# S3.net
KiCad netlist of a schematic drawn in EasyEDA Pro
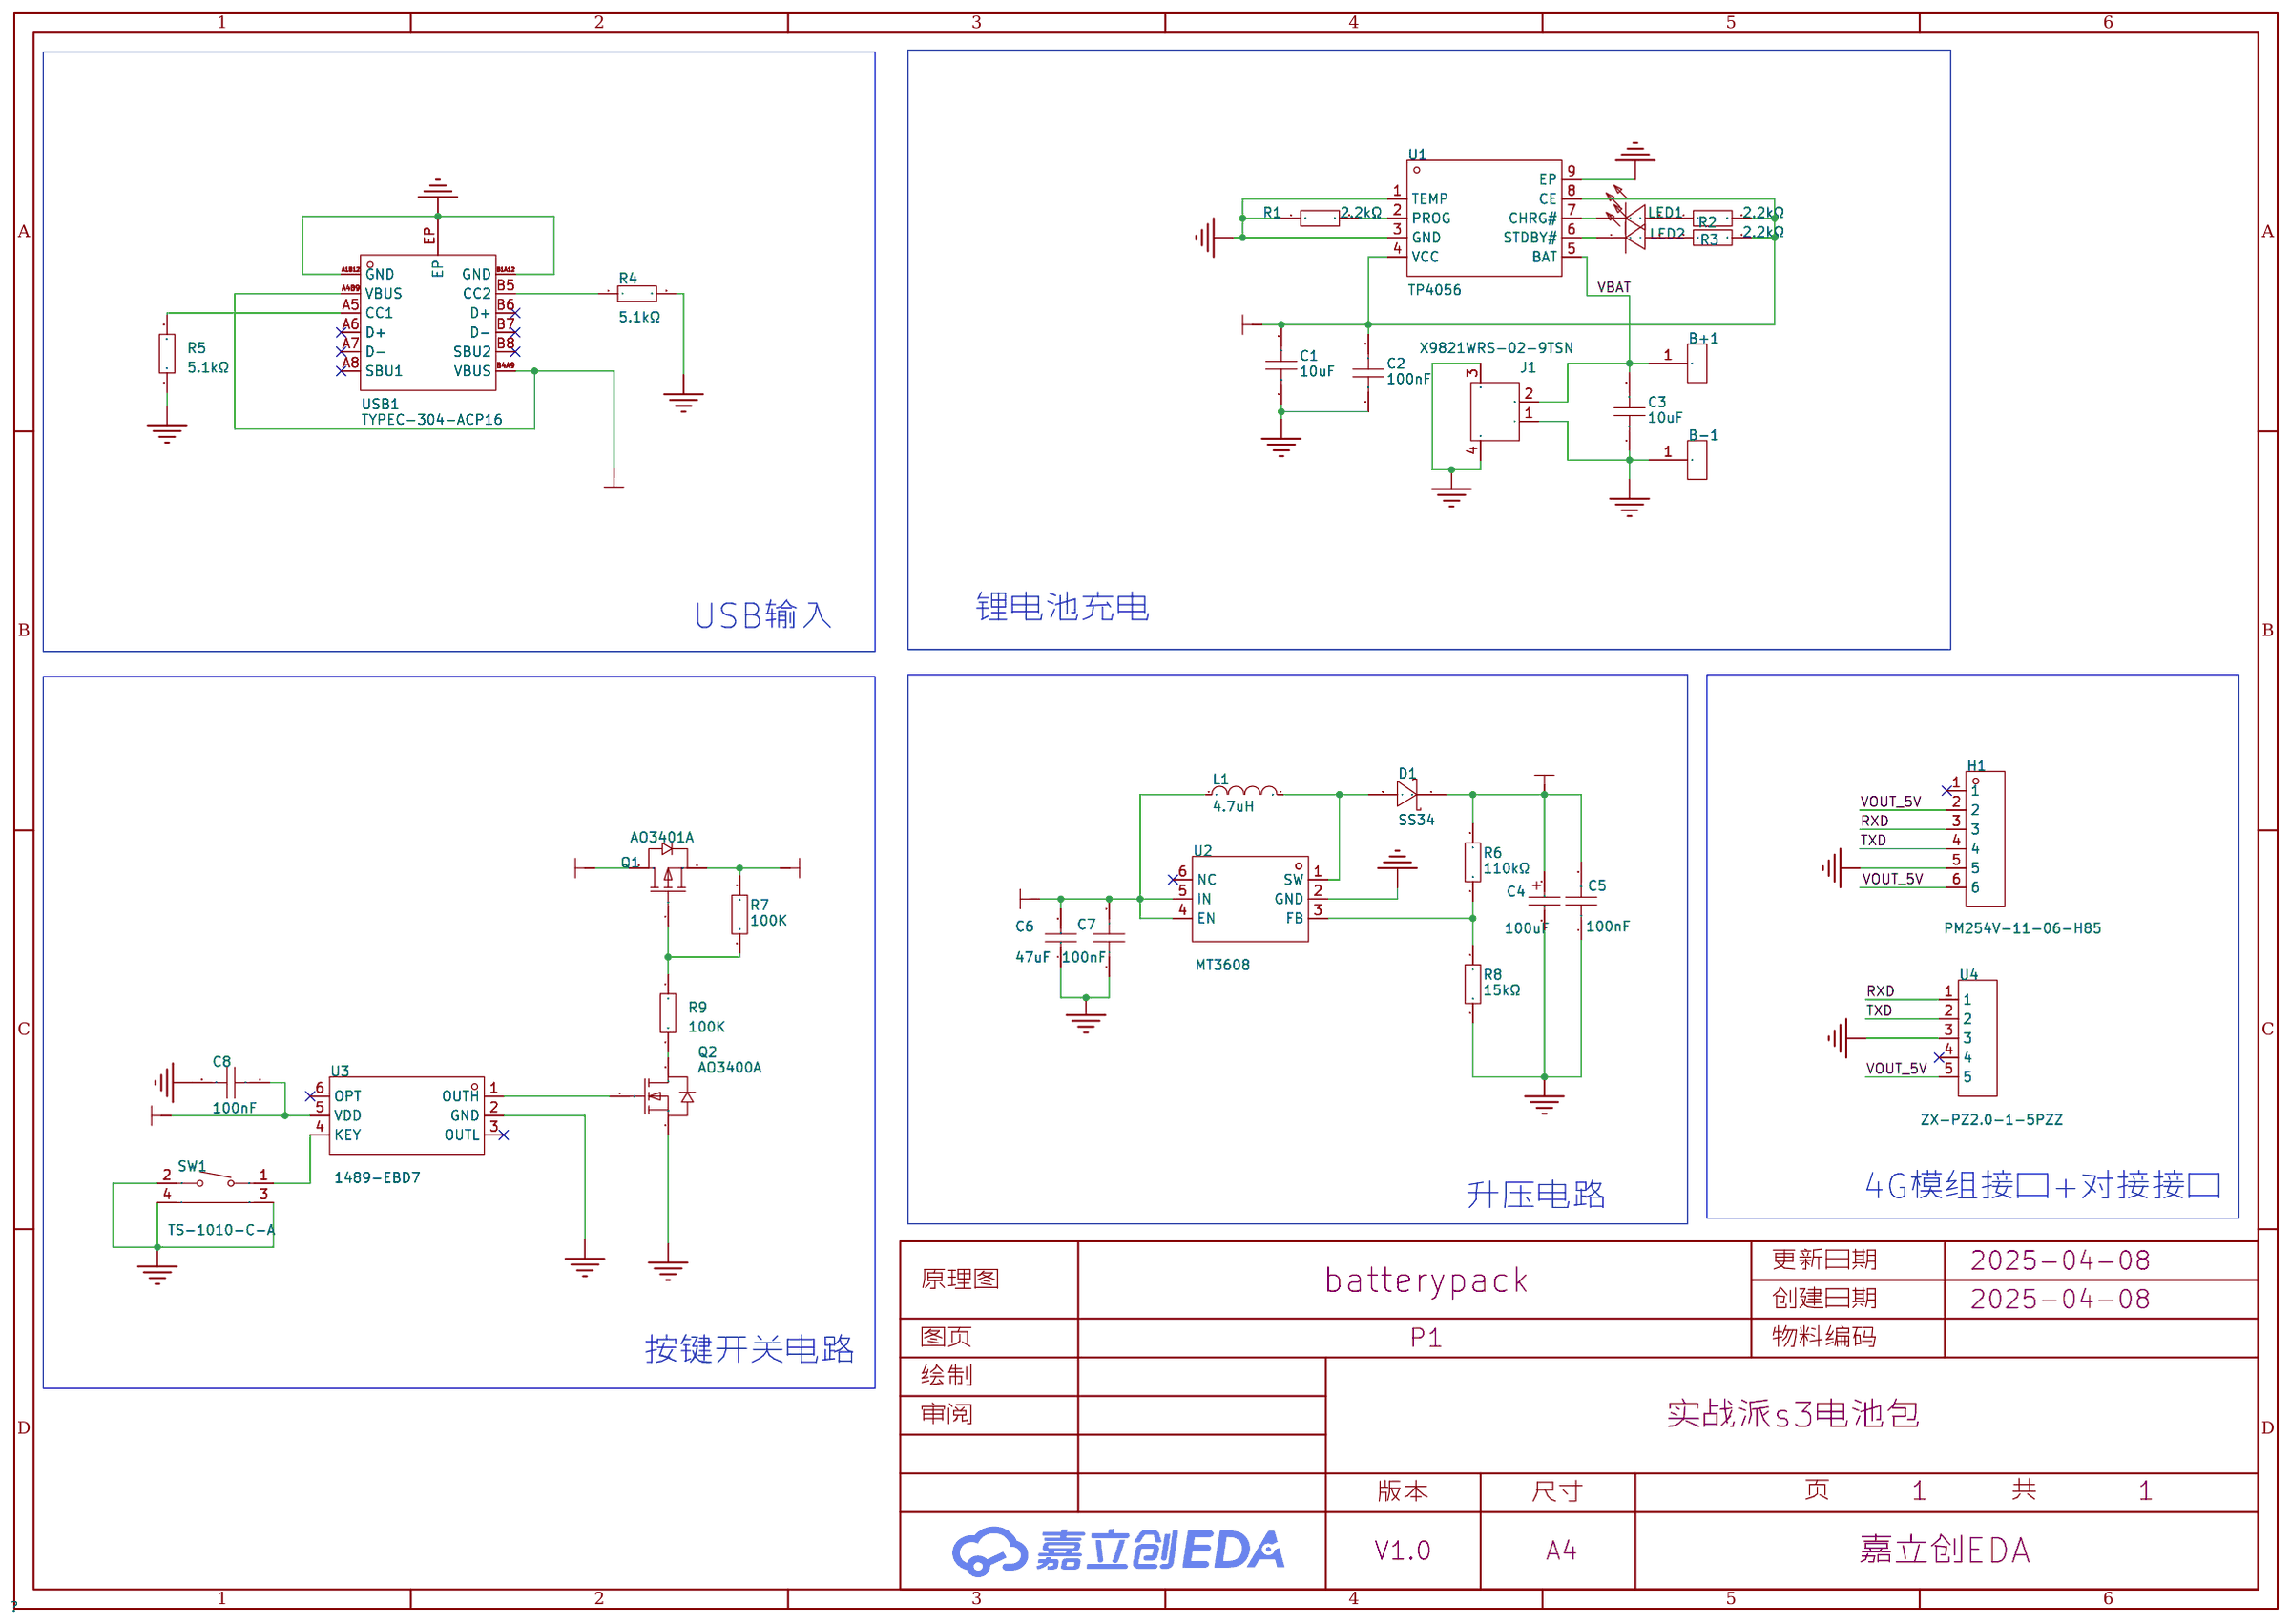
[diagram p0: schematic sheet]

(export (version "E")
  (design (tool "Eeschema 10.0.6"))
  (components
    (comp (ref "B+1")
      (value "~")
      (footprint "easyedapro:test_point")
      (libsource (lib "easyedapro") (part "test_point"))
    )
    (comp (ref "B-1")
      (value "~")
      (footprint "easyedapro:test_point")
      (libsource (lib "easyedapro") (part "test_point"))
    )
    (comp (ref "C1")
      (value "10uF")
      (fields
        (field (name "Manufacturer Part") "CL10A106KP8NNNC")
        (field (name "Manufacturer") "SAMSUNG(三星)")
      )
      (libsource (lib "easyedapro") (part "CL21A106KAYNNNE"))
    )
    (comp (ref "C2")
      (value "100nF")
      (footprint "easyedapro:C0402")
      (description "容值:100nF;精度:±10%;额定电压:50V;材质(温度系数):X7R;")
      (fields
        (field (name "Manufacturer Part") "CL05B104KB54PNC")
        (field (name "Manufacturer") "SAMSUNG(三星)")
      )
      (libsource (lib "easyedapro") (part "CL05B104KB54PNC"))
    )
    (comp (ref "C3")
      (value "10uF")
      (fields
        (field (name "Manufacturer Part") "CL10A106KP8NNNC")
        (field (name "Manufacturer") "SAMSUNG(三星)")
      )
      (libsource (lib "easyedapro") (part "CL21A106KAYNNNE"))
    )
    (comp (ref "C4")
      (value "100uF")
      (footprint "easyedapro:CASE-B_3528")
      (description "容值:100uF;精度:±10%;额定电压:6.3V;等效串联电阻:1.7Ω@100kHz;")
      (fields (field (name "Manufacturer Part") "TAJB107K006RNJ") (field (name "Manufacturer") "Kyocera AVX"))
      (libsource (lib "easyedapro") (part "TAJB107K006RNJ"))
    )
    (comp (ref "C5")
      (value "100nF")
      (fields
        (field (name "Manufacturer Part") "CL05B104KB54PNC")
        (field (name "Manufacturer") "SAMSUNG(三星)")
      )
      (libsource (lib "easyedapro") (part "CGA0603X7R104K500JT"))
    )
    (comp (ref "C6")
      (value "47uF")
      (footprint "easyedapro:C0805")
      (description "容值:47uF;精度:±20%;额定电压:6.3V;材质(温度系数):X5R;")
      (fields
        (field (name "Manufacturer Part") "CL21A476MQYNNNE")
        (field (name "Manufacturer") "SAMSUNG(三星)")
      )
      (libsource (lib "easyedapro") (part "CL21A476MQYNNNE"))
    )
    (comp (ref "C7")
      (value "100nF")
      (fields
        (field (name "Manufacturer Part") "CL05B104KB54PNC")
        (field (name "Manufacturer") "SAMSUNG(三星)")
      )
      (libsource (lib "easyedapro") (part "CGA0603X7R104K500JT"))
    )
    (comp (ref "C8")
      (value "100nF")
      (footprint "easyedapro:C0402")
      (libsource (lib "easyedapro") (part "CapAcitance"))
    )
    (comp (ref "D1")
      (value "SS34")
      (footprint "easyedapro:SMA_L4.3-W2.6-LS5.2-RD")
      (description "二极管配置:独立式;正向压降(Vf):550mV@3A;直流反向耐压(Vr):40V;整流电流:3A;")
      (fields (field (name "Manufacturer") "MDD(辰达半导体)"))
      (libsource (lib "easyedapro") (part "SS34_C8678"))
    )
    (comp (ref "H1")
      (value "PM254V-11-06-H85")
      (footprint "easyedapro:HDR-TH_6P-P2.54-V-F")
      (fields (field (name "Manufacturer") "XFCN(兴飞)"))
      (libsource (lib "easyedapro") (part "PM254V-11-06-H85"))
    )
    (comp (ref "J1")
      (value "X9821WRS-02-9TSN")
      (footprint "easyedapro:CONN-SMD_2P-P1.25_X9821WRS-02-9TSN")
      (fields (field (name "Manufacturer") "XKB Connectivity(中国星坤)"))
      (libsource (lib "easyedapro") (part "X9821WRS-02-9TSN"))
    )
    (comp (ref "L1")
      (value "4.7uH")
      (fields (field (name "Manufacturer Part") "FXL0420-4R7-M") (field (name "Manufacturer") "cjiang(长江微电)"))
      (libsource (lib "easyedapro") (part "FXL0630-220-M"))
    )
    (comp (ref "LED1")
      (value "KT-0603R")
      (footprint "easyedapro:LED0603-RD")
      (description "发光颜色:红色;功率:-;正向电流:-;主波长:-;二极管配置:-;透镜颜色:-;色温:-;发光角度:-;载带方式:-;工作温度:-40°C~+85°C;")
      (fields (field (name "Manufacturer") "KENTO"))
      (libsource (lib "easyedapro") (part "KT-0603R"))
    )
    (comp (ref "LED2")
      (value "KT-0603G")
      (footprint "easyedapro:LED0603-RD")
      (description "发光颜色:翠绿色;")
      (fields (field (name "Manufacturer") "KENTO"))
      (libsource (lib "easyedapro") (part "0603 Green 509-620mcd"))
    )
    (comp (ref "Q1")
      (value "AO3401A")
      (footprint "easyedapro:SOT-23_L2.9-W1.3-P1.90-LS2.4-BR")
      (fields (field (name "Manufacturer") "AOS"))
      (libsource (lib "easyedapro") (part "AO3401A"))
    )
    (comp (ref "Q2")
      (value "AO3400A")
      (footprint "easyedapro:SOT-23-3_L2.9-W1.3-P1.90-LS2.4-BR")
      (fields (field (name "Manufacturer") "AOS"))
      (libsource (lib "easyedapro") (part "AO3400A"))
    )
    (comp (ref "R1")
      (value "2.2kΩ")
      (footprint "easyedapro:R0402")
      (fields
        (field (name "Manufacturer Part") "0402WGF2201TCE")
        (field (name "Manufacturer") "UNI-ROYAL(厚声)")
      )
      (libsource (lib "easyedapro") (part "电阻"))
    )
    (comp (ref "R2")
      (value "2.2kΩ")
      (footprint "easyedapro:R0402")
      (fields
        (field (name "Manufacturer Part") "0402WGF2201TCE")
        (field (name "Manufacturer") "UNI-ROYAL(厚声)")
      )
      (libsource (lib "easyedapro") (part "电阻"))
    )
    (comp (ref "R3")
      (value "2.2kΩ")
      (footprint "easyedapro:R0402")
      (fields
        (field (name "Manufacturer Part") "0402WGF2201TCE")
        (field (name "Manufacturer") "UNI-ROYAL(厚声)")
      )
      (libsource (lib "easyedapro") (part "电阻"))
    )
    (comp (ref "R4")
      (value "5.1kΩ")
      (footprint "easyedapro:R0402")
      (description "电阻类型:厚膜电阻;阻值:5.1kΩ;精度:±1%;功率:62.5mW;最大工作电压:50V;温度系数:±100ppm/℃;")
      (fields
        (field (name "Manufacturer Part") "0402WGF5101TCE")
        (field (name "Manufacturer") "UNI-ROYAL(厚声)")
      )
      (libsource (lib "easyedapro") (part "0402WGF5101TCE"))
    )
    (comp (ref "R5")
      (value "5.1kΩ")
      (footprint "easyedapro:R0402")
      (description "电阻类型:厚膜电阻;阻值:5.1kΩ;精度:±1%;功率:62.5mW;最大工作电压:50V;温度系数:±100ppm/℃;")
      (fields
        (field (name "Manufacturer Part") "0402WGF5101TCE")
        (field (name "Manufacturer") "UNI-ROYAL(厚声)")
      )
      (libsource (lib "easyedapro") (part "0402WGF5101TCE"))
    )
    (comp (ref "R6")
      (value "110kΩ")
      (description "电阻类型:厚膜电阻;阻值:100kΩ;精度:±1%;功率:62.5mW;最大工作电压:50V;温度系数:±100ppm/℃;")
      (fields
        (field (name "Manufacturer Part") "0402WGF1003TCE")
        (field (name "Manufacturer") "UNI-ROYAL(厚声)")
      )
      (libsource (lib "easyedapro") (part "0603WAF1203T5E"))
    )
    (comp (ref "R7") (value "100K") (footprint "easyedapro:R0402") (libsource (lib "easyedapro") (part "电阻")))
    (comp (ref "R8")
      (value "15kΩ")
      (fields
        (field (name "Manufacturer Part") "0402WGF1502TCE")
        (field (name "Manufacturer") "UNI-ROYAL(厚声)")
      )
      (libsource (lib "easyedapro") (part "0603WAF1502T5E"))
    )
    (comp (ref "R9") (value "100K") (footprint "easyedapro:R0402") (libsource (lib "easyedapro") (part "电阻")))
    (comp (ref "SW1")
      (value "TS-1010-C-A")
      (footprint "easyedapro:KEY-SMD_TX-1010-X-X")
      (fields (field (name "Manufacturer") "XKB Connectivity(中国星坤)"))
      (libsource (lib "easyedapro") (part "TS-1010-C-A"))
    )
    (comp (ref "U1")
      (value "TP4056")
      (footprint "easyedapro:ESOP-8_L4.9-W3.9-P1.27-LS6.0-BL-EP")
      (fields (field (name "Manufacturer") "UMW(友台半导体)"))
      (libsource (lib "easyedapro") (part "TP4056_C725790"))
    )
    (comp (ref "U2")
      (value "MT3608")
      (footprint "easyedapro:SOT-23-6_L2.9-W1.6-P0.95-LS2.8-BL")
      (description "功能类型:升压型;输出类型:可调;工作电压:2V~24V;输出电压:28V;输出电流:2A;")
      (fields (field (name "Manufacturer") "西安航天民芯"))
      (libsource (lib "easyedapro") (part "MT3608"))
    )
    (comp (ref "U3")
      (value "1489-EBD7")
      (footprint "easyedapro:SOT-23-6_L2.9-W1.6-P0.95-LS2.8-BL")
      (description "开关IC  长按 1.5 秒开关机")
      (fields (field (name "Manufacturer") "深圳丽晶微"))
      (libsource (lib "easyedapro") (part "1489-EBD7"))
    )
    (comp (ref "U4")
      (value "ZX-PZ2.0-1-5PZZ")
      (footprint "easyedapro:HDR-TH_5P-P2.00-V-M")
      (fields (field (name "Manufacturer") "Megastar(兆星)"))
      (libsource (lib "easyedapro") (part "ZX-PZ2.0-1-5PZZ"))
    )
    (comp (ref "USB1")
      (value "TYPEC-304-ACP16")
      (footprint "easyedapro:USB-C-SMD_TYPE-C-16P-1")
      (fields (field (name "Manufacturer") "XUNPU(讯普)"))
      (libsource (lib "easyedapro") (part "TYPEC-304-ACP16"))
    )
  )
  (nets
    (net (code "1") (name "/RXD") (class "Default")
      (node (ref "H1") (pin "3") (pinfunction "3_3") (pintype "unspecified"))
      (node (ref "U4") (pin "1") (pinfunction "1_1") (pintype "unspecified"))
    )
    (net (code "2") (name "/TXD") (class "Default")
      (node (ref "H1") (pin "4") (pinfunction "4_4") (pintype "unspecified"))
      (node (ref "U4") (pin "2") (pinfunction "2_2") (pintype "unspecified"))
    )
    (net (code "3") (name "GND") (class "Default")
      (node (ref "B-1") (pin "1") (pinfunction "1_1") (pintype "input"))
      (node (ref "C1") (pin "1") (pinfunction "1_1") (pintype "unspecified"))
      (node (ref "C2") (pin "1") (pinfunction "1_1") (pintype "unspecified"))
      (node (ref "C3") (pin "1") (pinfunction "1_1") (pintype "unspecified"))
      (node (ref "C4") (pin "2") (pinfunction "2_2") (pintype "input"))
      (node (ref "C5") (pin "1") (pinfunction "1_1") (pintype "unspecified"))
      (node (ref "C6") (pin "1") (pinfunction "1_1") (pintype "input"))
      (node (ref "C7") (pin "1") (pinfunction "1_1") (pintype "unspecified"))
      (node (ref "C8") (pin "2") (pinfunction "2_2") (pintype "input"))
      (node (ref "H1") (pin "5") (pinfunction "5_5") (pintype "unspecified"))
      (node (ref "J1") (pin "1") (pinfunction "1_1") (pintype "input"))
      (node (ref "J1") (pin "3") (pinfunction "3_3") (pintype "input"))
      (node (ref "J1") (pin "4") (pinfunction "4_4") (pintype "input"))
      (node (ref "Q2") (pin "2") (pinfunction "S_2") (pintype "unspecified"))
      (node (ref "R1") (pin "1") (pinfunction "1_1") (pintype "input"))
      (node (ref "R4") (pin "2") (pinfunction "2_2") (pintype "input"))
      (node (ref "R5") (pin "1") (pinfunction "1_1") (pintype "input"))
      (node (ref "R8") (pin "1") (pinfunction "1_1") (pintype "input"))
      (node (ref "SW1") (pin "2") (pinfunction "2_2") (pintype "unspecified"))
      (node (ref "SW1") (pin "3") (pinfunction "3_3") (pintype "unspecified"))
      (node (ref "SW1") (pin "4") (pinfunction "4_4") (pintype "unspecified"))
      (node (ref "U1") (pin "1") (pinfunction "TEMP_1") (pintype "unspecified"))
      (node (ref "U1") (pin "3") (pinfunction "GND_3") (pintype "unspecified"))
      (node (ref "U1") (pin "9") (pinfunction "EP_9") (pintype "unspecified"))
      (node (ref "U2") (pin "2") (pinfunction "GND_2") (pintype "unspecified"))
      (node (ref "U3") (pin "2") (pinfunction "GND_2") (pintype "input"))
      (node (ref "U4") (pin "3") (pinfunction "3_3") (pintype "unspecified"))
      (node (ref "USB1") (pin "A1B12") (pinfunction "GND_A1B12") (pintype "unspecified"))
      (node (ref "USB1") (pin "B1A12") (pinfunction "GND_B1A12") (pintype "unspecified"))
      (node (ref "USB1") (pin "EP") (pinfunction "EP_EP") (pintype "unspecified"))
    )
    (net (code "4") (name "Net-(D1-A)") (class "Default")
      (node (ref "D1") (pin "2") (pinfunction "A_2") (pintype "unspecified"))
      (node (ref "L1") (pin "2") (pinfunction "2_2") (pintype "unspecified"))
      (node (ref "U2") (pin "1") (pinfunction "SW_1") (pintype "unspecified"))
    )
    (net (code "5") (name "Net-(LED1-A)") (class "Default")
      (node (ref "LED1") (pin "2") (pinfunction "A_2") (pintype "unspecified"))
      (node (ref "R2") (pin "1") (pinfunction "1_1") (pintype "input"))
    )
    (net (code "6") (name "Net-(LED1-K)") (class "Default")
      (node (ref "LED1") (pin "1") (pinfunction "K_1") (pintype "unspecified"))
      (node (ref "U1") (pin "7") (pinfunction "CHRG#_7") (pintype "unspecified"))
    )
    (net (code "7") (name "Net-(LED2-A)") (class "Default")
      (node (ref "LED2") (pin "2") (pinfunction "A_2") (pintype "unspecified"))
      (node (ref "R3") (pin "1") (pinfunction "1_1") (pintype "input"))
    )
    (net (code "8") (name "Net-(LED2-K)") (class "Default")
      (node (ref "LED2") (pin "1") (pinfunction "K_1") (pintype "unspecified"))
      (node (ref "U1") (pin "6") (pinfunction "STDBY#_6") (pintype "unspecified"))
    )
    (net (code "9") (name "Net-(Q1-G)") (class "Default")
      (node (ref "Q1") (pin "1") (pinfunction "G_1") (pintype "input"))
      (node (ref "R7") (pin "1") (pinfunction "1_1") (pintype "input"))
      (node (ref "R9") (pin "1") (pinfunction "1_1") (pintype "input"))
    )
    (net (code "10") (name "Net-(Q2-D)") (class "Default")
      (node (ref "Q2") (pin "3") (pinfunction "D_3") (pintype "unspecified"))
      (node (ref "R9") (pin "2") (pinfunction "2_2") (pintype "input"))
    )
    (net (code "11") (name "Net-(Q2-G)") (class "Default")
      (node (ref "Q2") (pin "1") (pinfunction "G_1") (pintype "unspecified"))
      (node (ref "U3") (pin "1") (pinfunction "OUTH_1") (pintype "input"))
    )
    (net (code "12") (name "Net-(U1-PROG)") (class "Default")
      (node (ref "R1") (pin "2") (pinfunction "2_2") (pintype "input"))
      (node (ref "U1") (pin "2") (pinfunction "PROG_2") (pintype "unspecified"))
    )
    (net (code "13") (name "Net-(U2-FB)") (class "Default")
      (node (ref "R6") (pin "1") (pinfunction "1_1") (pintype "input"))
      (node (ref "R8") (pin "2") (pinfunction "2_2") (pintype "input"))
      (node (ref "U2") (pin "3") (pinfunction "FB_3") (pintype "unspecified"))
    )
    (net (code "14") (name "Net-(U3-KEY)") (class "Default")
      (node (ref "SW1") (pin "1") (pinfunction "1_1") (pintype "unspecified"))
      (node (ref "U3") (pin "4") (pinfunction "KEY_4") (pintype "input"))
    )
    (net (code "15") (name "Net-(USB1-CC1)") (class "Default")
      (node (ref "R5") (pin "2") (pinfunction "2_2") (pintype "input"))
      (node (ref "USB1") (pin "A5") (pinfunction "CC1_A5") (pintype "unspecified"))
    )
    (net (code "16") (name "Net-(USB1-CC2)") (class "Default")
      (node (ref "R4") (pin "1") (pinfunction "1_1") (pintype "input"))
      (node (ref "USB1") (pin "B5") (pinfunction "CC2_B5") (pintype "unspecified"))
    )
    (net (code "17") (name "USB_5V") (class "Default")
      (node (ref "C1") (pin "2") (pinfunction "2_2") (pintype "unspecified"))
      (node (ref "C2") (pin "2") (pinfunction "2_2") (pintype "unspecified"))
      (node (ref "R2") (pin "2") (pinfunction "2_2") (pintype "input"))
      (node (ref "R3") (pin "2") (pinfunction "2_2") (pintype "input"))
      (node (ref "U1") (pin "4") (pinfunction "VCC_4") (pintype "unspecified"))
      (node (ref "U1") (pin "8") (pinfunction "CE_8") (pintype "unspecified"))
      (node (ref "USB1") (pin "A4B9") (pinfunction "VBUS_A4B9") (pintype "unspecified"))
      (node (ref "USB1") (pin "B4A9") (pinfunction "VBUS_B4A9") (pintype "unspecified"))
    )
    (net (code "18") (name "VBAT") (class "Default")
      (node (ref "B+1") (pin "1") (pinfunction "1_1") (pintype "input"))
      (node (ref "C3") (pin "2") (pinfunction "2_2") (pintype "unspecified"))
      (node (ref "C8") (pin "1") (pinfunction "1_1") (pintype "input"))
      (node (ref "J1") (pin "2") (pinfunction "2_2") (pintype "input"))
      (node (ref "Q1") (pin "2") (pinfunction "S_2") (pintype "input"))
      (node (ref "R7") (pin "2") (pinfunction "2_2") (pintype "input"))
      (node (ref "U1") (pin "5") (pinfunction "BAT_5") (pintype "unspecified"))
      (node (ref "U3") (pin "5") (pinfunction "VDD_5") (pintype "input"))
    )
    (net (code "19") (name "VBAT_OUT") (class "Default")
      (node (ref "C6") (pin "2") (pinfunction "2_2") (pintype "input"))
      (node (ref "C7") (pin "2") (pinfunction "2_2") (pintype "unspecified"))
      (node (ref "L1") (pin "1") (pinfunction "1_1") (pintype "unspecified"))
      (node (ref "Q1") (pin "3") (pinfunction "D_3") (pintype "input"))
      (node (ref "U2") (pin "4") (pinfunction "EN_4") (pintype "unspecified"))
      (node (ref "U2") (pin "5") (pinfunction "IN_5") (pintype "unspecified"))
    )
    (net (code "20") (name "VOUT_5V") (class "Default")
      (node (ref "C4") (pin "1") (pinfunction "1_1") (pintype "input"))
      (node (ref "C5") (pin "2") (pinfunction "2_2") (pintype "unspecified"))
      (node (ref "D1") (pin "1") (pinfunction "K_1") (pintype "unspecified"))
      (node (ref "H1") (pin "2") (pinfunction "2_2") (pintype "unspecified"))
      (node (ref "H1") (pin "6") (pinfunction "6_6") (pintype "unspecified"))
      (node (ref "R6") (pin "2") (pinfunction "2_2") (pintype "input"))
      (node (ref "U4") (pin "5") (pinfunction "5_5") (pintype "unspecified"))
    )
    (net (code "21") (name "unconnected-(H1-Pad1)") (class "Default")
      (node (ref "H1") (pin "1") (pinfunction "1_1") (pintype "unspecified+no_connect"))
    )
    (net (code "22") (name "unconnected-(U2-NC-Pad6)") (class "Default")
      (node (ref "U2") (pin "6") (pinfunction "NC_6") (pintype "unspecified+no_connect"))
    )
    (net (code "23") (name "unconnected-(U3-OPT-Pad6)") (class "Default")
      (node (ref "U3") (pin "6") (pinfunction "OPT_6") (pintype "input+no_connect"))
    )
    (net (code "24") (name "unconnected-(U3-OUTL-Pad3)") (class "Default")
      (node (ref "U3") (pin "3") (pinfunction "OUTL_3") (pintype "input+no_connect"))
    )
    (net (code "25") (name "unconnected-(U4-Pad4)") (class "Default")
      (node (ref "U4") (pin "4") (pinfunction "4_4") (pintype "unspecified+no_connect"))
    )
    (net (code "26") (name "unconnected-(USB1-D+-PadA6)") (class "Default")
      (node (ref "USB1") (pin "A6") (pinfunction "D+_A6") (pintype "unspecified+no_connect"))
    )
    (net (code "27") (name "unconnected-(USB1-D+-PadB6)") (class "Default")
      (node (ref "USB1") (pin "B6") (pinfunction "D+_B6") (pintype "unspecified+no_connect"))
    )
    (net (code "28") (name "unconnected-(USB1-D--PadA7)") (class "Default")
      (node (ref "USB1") (pin "A7") (pinfunction "D-_A7") (pintype "unspecified+no_connect"))
    )
    (net (code "29") (name "unconnected-(USB1-D--PadB7)") (class "Default")
      (node (ref "USB1") (pin "B7") (pinfunction "D-_B7") (pintype "unspecified+no_connect"))
    )
    (net (code "30") (name "unconnected-(USB1-SBU1-PadA8)") (class "Default")
      (node (ref "USB1") (pin "A8") (pinfunction "SBU1_A8") (pintype "unspecified+no_connect"))
    )
    (net (code "31") (name "unconnected-(USB1-SBU2-PadB8)") (class "Default")
      (node (ref "USB1") (pin "B8") (pinfunction "SBU2_B8") (pintype "unspecified+no_connect"))
    )
  )
)
